# BLDC-MOSFET.net
KiCad netlist of a schematic drawn in Altium Designer
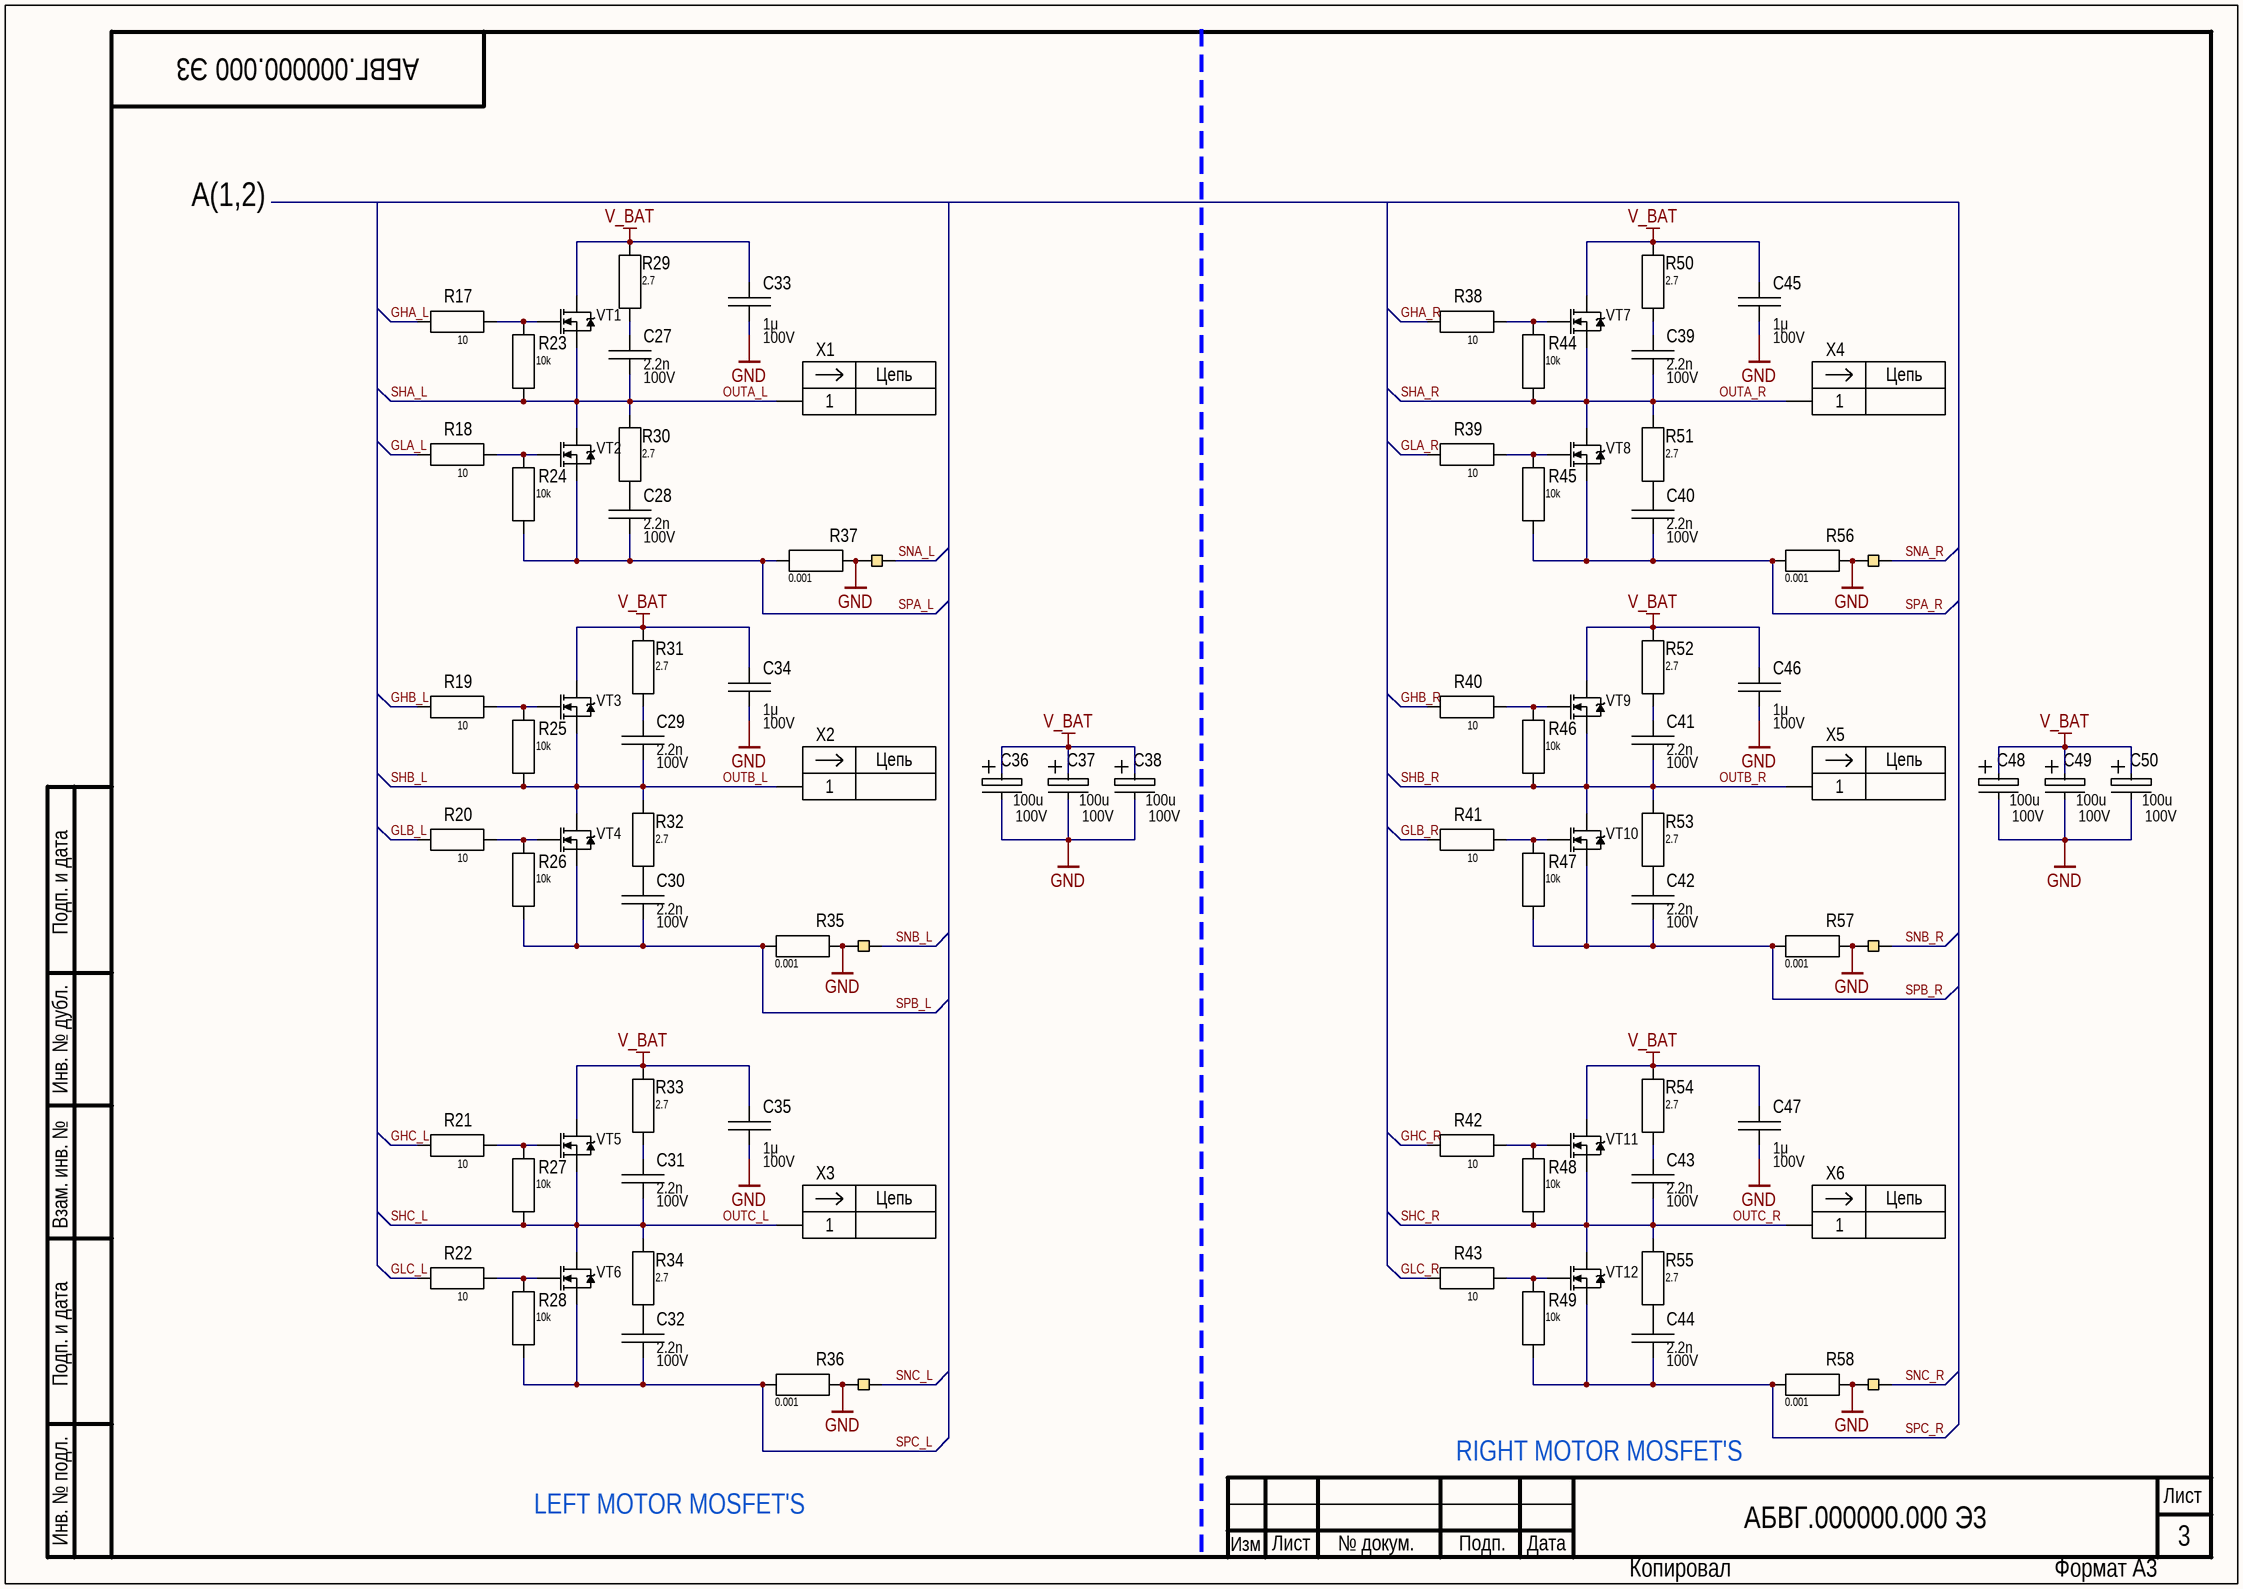
[diagram p0: BLDC-MOSFET.SchDoc]

(export (version "E")
  (design (tool "Eeschema 10.0.6"))
  (components
    (comp (ref "C27")
      (value "2.2n")
      (footprint "StandardCase:CAP: 0603")
      (fields
        (field (name "VALUEMANUFACTURERPARTNUMBER") "Ceramic capacitor, 2.2n, X7R, ±10%, 100V, 0603, -55...+125°C")
        (field (name "TOLERANCE") "±10%")
        (field (name "VOLTAGE") "100V")
      )
      (libsource (lib "Capacitor") (part "Ceramic_0603"))
    )
    (comp (ref "C28")
      (value "2.2n")
      (footprint "StandardCase:CAP: 0603")
      (fields
        (field (name "VALUEMANUFACTURERPARTNUMBER") "Ceramic capacitor, 2.2n, X7R, ±10%, 100V, 0603, -55...+125°C")
        (field (name "TOLERANCE") "±10%")
        (field (name "VOLTAGE") "100V")
      )
      (libsource (lib "Capacitor") (part "Ceramic_0603"))
    )
    (comp (ref "C29")
      (value "2.2n")
      (footprint "StandardCase:CAP: 0603")
      (fields
        (field (name "VALUEMANUFACTURERPARTNUMBER") "Ceramic capacitor, 2.2n, X7R, ±10%, 100V, 0603, -55...+125°C")
        (field (name "TOLERANCE") "±10%")
        (field (name "VOLTAGE") "100V")
      )
      (libsource (lib "Capacitor") (part "Ceramic_0603"))
    )
    (comp (ref "C30")
      (value "2.2n")
      (footprint "StandardCase:CAP: 0603")
      (fields
        (field (name "VALUEMANUFACTURERPARTNUMBER") "Ceramic capacitor, 2.2n, X7R, ±10%, 100V, 0603, -55...+125°C")
        (field (name "TOLERANCE") "±10%")
        (field (name "VOLTAGE") "100V")
      )
      (libsource (lib "Capacitor") (part "Ceramic_0603"))
    )
    (comp (ref "C31")
      (value "2.2n")
      (footprint "StandardCase:CAP: 0603")
      (fields
        (field (name "VALUEMANUFACTURERPARTNUMBER") "Ceramic capacitor, 2.2n, X7R, ±10%, 100V, 0603, -55...+125°C")
        (field (name "TOLERANCE") "±10%")
        (field (name "VOLTAGE") "100V")
      )
      (libsource (lib "Capacitor") (part "Ceramic_0603"))
    )
    (comp (ref "C32")
      (value "2.2n")
      (footprint "StandardCase:CAP: 0603")
      (fields
        (field (name "VALUEMANUFACTURERPARTNUMBER") "Ceramic capacitor, 2.2n, X7R, ±10%, 100V, 0603, -55...+125°C")
        (field (name "TOLERANCE") "±10%")
        (field (name "VOLTAGE") "100V")
      )
      (libsource (lib "Capacitor") (part "Ceramic_0603"))
    )
    (comp (ref "C33")
      (value "1μ")
      (footprint "StandardCase:CAP: 1206")
      (fields
        (field (name "VALUEMANUFACTURERPARTNUMBER") "Ceramic capacitor, 1μ, X7R, ±10%, 100V, 1206, -55...+125°C")
        (field (name "TOLERANCE") "±10%")
        (field (name "VOLTAGE") "100V")
      )
      (libsource (lib "Capacitor") (part "Ceramic_1206"))
    )
    (comp (ref "C34")
      (value "1μ")
      (footprint "StandardCase:CAP: 1206")
      (fields
        (field (name "VALUEMANUFACTURERPARTNUMBER") "Ceramic capacitor, 1μ, X7R, ±10%, 100V, 1206, -55...+125°C")
        (field (name "TOLERANCE") "±10%")
        (field (name "VOLTAGE") "100V")
      )
      (libsource (lib "Capacitor") (part "Ceramic_1206"))
    )
    (comp (ref "C35")
      (value "1μ")
      (footprint "StandardCase:CAP: 1206")
      (fields
        (field (name "VALUEMANUFACTURERPARTNUMBER") "Ceramic capacitor, 1μ, X7R, ±10%, 100V, 1206, -55...+125°C")
        (field (name "TOLERANCE") "±10%")
        (field (name "VOLTAGE") "100V")
      )
      (libsource (lib "Capacitor") (part "Ceramic_1206"))
    )
    (comp (ref "C36")
      (value "100u")
      (footprint "ECR1021")
      (description "ECR1021")
      (fields (field (name "PARTNUMBER") "B45196HM20-35 B-100u мкФ") (field (name "VOLTAGE") "100V"))
      (libsource (lib "capacitors") (part "ECR1021"))
    )
    (comp (ref "C37")
      (value "100u")
      (footprint "ECR1021")
      (description "ECR1021")
      (fields (field (name "PARTNUMBER") "B45196HM20-35 B-100u мкФ") (field (name "VOLTAGE") "100V"))
      (libsource (lib "capacitors") (part "ECR1021"))
    )
    (comp (ref "C38")
      (value "100u")
      (footprint "ECR1021")
      (description "ECR1021")
      (fields (field (name "PARTNUMBER") "B45196HM20-35 B-100u мкФ") (field (name "VOLTAGE") "100V"))
      (libsource (lib "capacitors") (part "ECR1021"))
    )
    (comp (ref "C39")
      (value "2.2n")
      (footprint "StandardCase:CAP: 0603")
      (fields
        (field (name "VALUEMANUFACTURERPARTNUMBER") "Ceramic capacitor, 2.2n, X7R, ±10%, 100V, 0603, -55...+125°C")
        (field (name "TOLERANCE") "±10%")
        (field (name "VOLTAGE") "100V")
      )
      (libsource (lib "Capacitor") (part "Ceramic_0603"))
    )
    (comp (ref "C40")
      (value "2.2n")
      (footprint "StandardCase:CAP: 0603")
      (fields
        (field (name "VALUEMANUFACTURERPARTNUMBER") "Ceramic capacitor, 2.2n, X7R, ±10%, 100V, 0603, -55...+125°C")
        (field (name "TOLERANCE") "±10%")
        (field (name "VOLTAGE") "100V")
      )
      (libsource (lib "Capacitor") (part "Ceramic_0603"))
    )
    (comp (ref "C41")
      (value "2.2n")
      (footprint "StandardCase:CAP: 0603")
      (fields
        (field (name "VALUEMANUFACTURERPARTNUMBER") "Ceramic capacitor, 2.2n, X7R, ±10%, 100V, 0603, -55...+125°C")
        (field (name "TOLERANCE") "±10%")
        (field (name "VOLTAGE") "100V")
      )
      (libsource (lib "Capacitor") (part "Ceramic_0603"))
    )
    (comp (ref "C42")
      (value "2.2n")
      (footprint "StandardCase:CAP: 0603")
      (fields
        (field (name "VALUEMANUFACTURERPARTNUMBER") "Ceramic capacitor, 2.2n, X7R, ±10%, 100V, 0603, -55...+125°C")
        (field (name "TOLERANCE") "±10%")
        (field (name "VOLTAGE") "100V")
      )
      (libsource (lib "Capacitor") (part "Ceramic_0603"))
    )
    (comp (ref "C43")
      (value "2.2n")
      (footprint "StandardCase:CAP: 0603")
      (fields
        (field (name "VALUEMANUFACTURERPARTNUMBER") "Ceramic capacitor, 2.2n, X7R, ±10%, 100V, 0603, -55...+125°C")
        (field (name "TOLERANCE") "±10%")
        (field (name "VOLTAGE") "100V")
      )
      (libsource (lib "Capacitor") (part "Ceramic_0603"))
    )
    (comp (ref "C44")
      (value "2.2n")
      (footprint "StandardCase:CAP: 0603")
      (fields
        (field (name "VALUEMANUFACTURERPARTNUMBER") "Ceramic capacitor, 2.2n, X7R, ±10%, 100V, 0603, -55...+125°C")
        (field (name "TOLERANCE") "±10%")
        (field (name "VOLTAGE") "100V")
      )
      (libsource (lib "Capacitor") (part "Ceramic_0603"))
    )
    (comp (ref "C45")
      (value "1μ")
      (footprint "StandardCase:CAP: 1206")
      (fields
        (field (name "VALUEMANUFACTURERPARTNUMBER") "Ceramic capacitor, 1μ, X7R, ±10%, 100V, 1206, -55...+125°C")
        (field (name "TOLERANCE") "±10%")
        (field (name "VOLTAGE") "100V")
      )
      (libsource (lib "Capacitor") (part "Ceramic_1206"))
    )
    (comp (ref "C46")
      (value "1μ")
      (footprint "StandardCase:CAP: 1206")
      (fields
        (field (name "VALUEMANUFACTURERPARTNUMBER") "Ceramic capacitor, 1μ, X7R, ±10%, 100V, 1206, -55...+125°C")
        (field (name "TOLERANCE") "±10%")
        (field (name "VOLTAGE") "100V")
      )
      (libsource (lib "Capacitor") (part "Ceramic_1206"))
    )
    (comp (ref "C47")
      (value "1μ")
      (footprint "StandardCase:CAP: 1206")
      (fields
        (field (name "VALUEMANUFACTURERPARTNUMBER") "Ceramic capacitor, 1μ, X7R, ±10%, 100V, 1206, -55...+125°C")
        (field (name "TOLERANCE") "±10%")
        (field (name "VOLTAGE") "100V")
      )
      (libsource (lib "Capacitor") (part "Ceramic_1206"))
    )
    (comp (ref "C48")
      (value "100u")
      (footprint "ECR1021")
      (description "ECR1021")
      (fields (field (name "PARTNUMBER") "B45196HM20-35 B-100u мкФ") (field (name "VOLTAGE") "100V"))
      (libsource (lib "capacitors") (part "ECR1021"))
    )
    (comp (ref "C49")
      (value "100u")
      (footprint "ECR1021")
      (description "ECR1021")
      (fields (field (name "PARTNUMBER") "B45196HM20-35 B-100u мкФ") (field (name "VOLTAGE") "100V"))
      (libsource (lib "capacitors") (part "ECR1021"))
    )
    (comp (ref "C50")
      (value "100u")
      (footprint "ECR1021")
      (description "ECR1021")
      (fields (field (name "PARTNUMBER") "B45196HM20-35 B-100u мкФ") (field (name "VOLTAGE") "100V"))
      (libsource (lib "capacitors") (part "ECR1021"))
    )
    (comp (ref "NT1") (value "~") (footprint "CON: NT") (libsource (lib "BKM_SCH_Lib") (part "NT")))
    (comp (ref "NT2") (value "~") (footprint "CON: NT") (libsource (lib "BKM_SCH_Lib") (part "NT")))
    (comp (ref "NT3") (value "~") (footprint "CON: NT") (libsource (lib "BKM_SCH_Lib") (part "NT")))
    (comp (ref "NT4") (value "~") (footprint "CON: NT") (libsource (lib "BKM_SCH_Lib") (part "NT")))
    (comp (ref "NT5") (value "~") (footprint "CON: NT") (libsource (lib "BKM_SCH_Lib") (part "NT")))
    (comp (ref "NT6") (value "~") (footprint "CON: NT") (libsource (lib "BKM_SCH_Lib") (part "NT")))
    (comp (ref "R17")
      (value "10")
      (footprint "RES: 0402")
      (fields (field (name "PARTNUMBER") "RC0402FR-071KL") (field (name "TOLERANCE") "1%"))
      (libsource (lib "Fider_Board_Lib") (part "RES 0402"))
    )
    (comp (ref "R18")
      (value "10")
      (footprint "RES: 0402")
      (fields (field (name "PARTNUMBER") "RC0402FR-071KL") (field (name "TOLERANCE") "1%"))
      (libsource (lib "Fider_Board_Lib") (part "RES 0402"))
    )
    (comp (ref "R19")
      (value "10")
      (footprint "RES: 0402")
      (fields (field (name "PARTNUMBER") "RC0402FR-071KL") (field (name "TOLERANCE") "1%"))
      (libsource (lib "Fider_Board_Lib") (part "RES 0402"))
    )
    (comp (ref "R20")
      (value "10")
      (footprint "RES: 0402")
      (fields (field (name "PARTNUMBER") "RC0402FR-071KL") (field (name "TOLERANCE") "1%"))
      (libsource (lib "Fider_Board_Lib") (part "RES 0402"))
    )
    (comp (ref "R21")
      (value "10")
      (footprint "RES: 0402")
      (fields (field (name "PARTNUMBER") "RC0402FR-071KL") (field (name "TOLERANCE") "1%"))
      (libsource (lib "Fider_Board_Lib") (part "RES 0402"))
    )
    (comp (ref "R22")
      (value "10")
      (footprint "RES: 0402")
      (fields (field (name "PARTNUMBER") "RC0402FR-071KL") (field (name "TOLERANCE") "1%"))
      (libsource (lib "Fider_Board_Lib") (part "RES 0402"))
    )
    (comp (ref "R23")
      (value "10k")
      (footprint "RES: 0402")
      (fields (field (name "TOLERANCE") "1%"))
      (libsource (lib "BKM_SCH_Lib") (part "RES 0402"))
    )
    (comp (ref "R24")
      (value "10k")
      (footprint "RES: 0402")
      (fields (field (name "TOLERANCE") "1%"))
      (libsource (lib "BKM_SCH_Lib") (part "RES 0402"))
    )
    (comp (ref "R25")
      (value "10k")
      (footprint "RES: 0402")
      (fields (field (name "TOLERANCE") "1%"))
      (libsource (lib "BKM_SCH_Lib") (part "RES 0402"))
    )
    (comp (ref "R26")
      (value "10k")
      (footprint "RES: 0402")
      (fields (field (name "TOLERANCE") "1%"))
      (libsource (lib "BKM_SCH_Lib") (part "RES 0402"))
    )
    (comp (ref "R27")
      (value "10k")
      (footprint "RES: 0402")
      (fields (field (name "TOLERANCE") "1%"))
      (libsource (lib "BKM_SCH_Lib") (part "RES 0402"))
    )
    (comp (ref "R28")
      (value "10k")
      (footprint "RES: 0402")
      (fields (field (name "TOLERANCE") "1%"))
      (libsource (lib "BKM_SCH_Lib") (part "RES 0402"))
    )
    (comp (ref "R29") (value "2.7") (footprint "RES: 0805") (libsource (lib "BKM_SCH_Lib") (part "RES 0805")))
    (comp (ref "R30") (value "2.7") (footprint "RES: 0805") (libsource (lib "BKM_SCH_Lib") (part "RES 0805")))
    (comp (ref "R31") (value "2.7") (footprint "RES: 0805") (libsource (lib "BKM_SCH_Lib") (part "RES 0805")))
    (comp (ref "R32") (value "2.7") (footprint "RES: 0805") (libsource (lib "BKM_SCH_Lib") (part "RES 0805")))
    (comp (ref "R33") (value "2.7") (footprint "RES: 0805") (libsource (lib "BKM_SCH_Lib") (part "RES 0805")))
    (comp (ref "R34") (value "2.7") (footprint "RES: 0805") (libsource (lib "BKM_SCH_Lib") (part "RES 0805")))
    (comp (ref "R35")
      (value "0.001")
      (footprint "RES: 2512")
      (fields (field (name "PARTNUMBER") "CST0612-FC-R001E"))
      (libsource (lib "Fider_Board_Lib") (part "RES 2512"))
    )
    (comp (ref "R36")
      (value "0.001")
      (footprint "RES: 2512")
      (fields (field (name "PARTNUMBER") "CST0612-FC-R001E"))
      (libsource (lib "Fider_Board_Lib") (part "RES 2512"))
    )
    (comp (ref "R37")
      (value "0.001")
      (footprint "RES: 2512")
      (fields (field (name "PARTNUMBER") "CST0612-FC-R001E"))
      (libsource (lib "Fider_Board_Lib") (part "RES 2512"))
    )
    (comp (ref "R38")
      (value "10")
      (footprint "RES: 0402")
      (fields (field (name "PARTNUMBER") "RC0402FR-071KL") (field (name "TOLERANCE") "1%"))
      (libsource (lib "Fider_Board_Lib") (part "RES 0402"))
    )
    (comp (ref "R39")
      (value "10")
      (footprint "RES: 0402")
      (fields (field (name "PARTNUMBER") "RC0402FR-071KL") (field (name "TOLERANCE") "1%"))
      (libsource (lib "Fider_Board_Lib") (part "RES 0402"))
    )
    (comp (ref "R40")
      (value "10")
      (footprint "RES: 0402")
      (fields (field (name "PARTNUMBER") "RC0402FR-071KL") (field (name "TOLERANCE") "1%"))
      (libsource (lib "Fider_Board_Lib") (part "RES 0402"))
    )
    (comp (ref "R41")
      (value "10")
      (footprint "RES: 0402")
      (fields (field (name "PARTNUMBER") "RC0402FR-071KL") (field (name "TOLERANCE") "1%"))
      (libsource (lib "Fider_Board_Lib") (part "RES 0402"))
    )
    (comp (ref "R42")
      (value "10")
      (footprint "RES: 0402")
      (fields (field (name "PARTNUMBER") "RC0402FR-071KL") (field (name "TOLERANCE") "1%"))
      (libsource (lib "Fider_Board_Lib") (part "RES 0402"))
    )
    (comp (ref "R43")
      (value "10")
      (footprint "RES: 0402")
      (fields (field (name "PARTNUMBER") "RC0402FR-071KL") (field (name "TOLERANCE") "1%"))
      (libsource (lib "Fider_Board_Lib") (part "RES 0402"))
    )
    (comp (ref "R44")
      (value "10k")
      (footprint "RES: 0402")
      (fields (field (name "TOLERANCE") "1%"))
      (libsource (lib "BKM_SCH_Lib") (part "RES 0402"))
    )
    (comp (ref "R45")
      (value "10k")
      (footprint "RES: 0402")
      (fields (field (name "TOLERANCE") "1%"))
      (libsource (lib "BKM_SCH_Lib") (part "RES 0402"))
    )
    (comp (ref "R46")
      (value "10k")
      (footprint "RES: 0402")
      (fields (field (name "TOLERANCE") "1%"))
      (libsource (lib "BKM_SCH_Lib") (part "RES 0402"))
    )
    (comp (ref "R47")
      (value "10k")
      (footprint "RES: 0402")
      (fields (field (name "TOLERANCE") "1%"))
      (libsource (lib "BKM_SCH_Lib") (part "RES 0402"))
    )
    (comp (ref "R48")
      (value "10k")
      (footprint "RES: 0402")
      (fields (field (name "TOLERANCE") "1%"))
      (libsource (lib "BKM_SCH_Lib") (part "RES 0402"))
    )
    (comp (ref "R49")
      (value "10k")
      (footprint "RES: 0402")
      (fields (field (name "TOLERANCE") "1%"))
      (libsource (lib "BKM_SCH_Lib") (part "RES 0402"))
    )
    (comp (ref "R50") (value "2.7") (footprint "RES: 0805") (libsource (lib "BKM_SCH_Lib") (part "RES 0805")))
    (comp (ref "R51") (value "2.7") (footprint "RES: 0805") (libsource (lib "BKM_SCH_Lib") (part "RES 0805")))
    (comp (ref "R52") (value "2.7") (footprint "RES: 0805") (libsource (lib "BKM_SCH_Lib") (part "RES 0805")))
    (comp (ref "R53") (value "2.7") (footprint "RES: 0805") (libsource (lib "BKM_SCH_Lib") (part "RES 0805")))
    (comp (ref "R54") (value "2.7") (footprint "RES: 0805") (libsource (lib "BKM_SCH_Lib") (part "RES 0805")))
    (comp (ref "R55") (value "2.7") (footprint "RES: 0805") (libsource (lib "BKM_SCH_Lib") (part "RES 0805")))
    (comp (ref "R56")
      (value "0.001")
      (footprint "RES: 2512")
      (fields (field (name "PARTNUMBER") "CST0612-FC-R001E"))
      (libsource (lib "Fider_Board_Lib") (part "RES 2512"))
    )
    (comp (ref "R57")
      (value "0.001")
      (footprint "RES: 2512")
      (fields (field (name "PARTNUMBER") "CST0612-FC-R001E"))
      (libsource (lib "Fider_Board_Lib") (part "RES 2512"))
    )
    (comp (ref "R58")
      (value "0.001")
      (footprint "RES: 2512")
      (fields (field (name "PARTNUMBER") "CST0612-FC-R001E"))
      (libsource (lib "Fider_Board_Lib") (part "RES 2512"))
    )
    (comp (ref "VT1")
      (value "~")
      (footprint "DirectFET MZ")
      (fields
        (field (name "MANUFACTURER") "Infineon Technologies")
        (field (name "VALUEMANUFACTURERPARTNUMBER") "MOSFET N-channel transistor, 150V, 35A, 9.1nC, 2.5W, 29mOhm, 756pF, DIRECTFET-MZ, -55...+150°C")
        (field (name "PARTNUMBER") "IRF6643TRPBF")
      )
      (libsource (lib "Transistor") (part "MOSFET_N_123"))
    )
    (comp (ref "VT2")
      (value "~")
      (footprint "DirectFET MZ")
      (fields
        (field (name "MANUFACTURER") "Infineon Technologies")
        (field (name "VALUEMANUFACTURERPARTNUMBER") "MOSFET N-channel transistor, 150V, 35A, 9.1nC, 2.5W, 29mOhm, 756pF, DIRECTFET-MZ, -55...+150°C")
        (field (name "PARTNUMBER") "IRF6643TRPBF")
      )
      (libsource (lib "Transistor") (part "MOSFET_N_123"))
    )
    (comp (ref "VT3")
      (value "~")
      (footprint "DirectFET MZ")
      (fields
        (field (name "MANUFACTURER") "Infineon Technologies")
        (field (name "VALUEMANUFACTURERPARTNUMBER") "MOSFET N-channel transistor, 150V, 35A, 9.1nC, 2.5W, 29mOhm, 756pF, DIRECTFET-MZ, -55...+150°C")
        (field (name "PARTNUMBER") "IRF6643TRPBF")
      )
      (libsource (lib "Transistor") (part "MOSFET_N_123"))
    )
    (comp (ref "VT4")
      (value "~")
      (footprint "DirectFET MZ")
      (fields
        (field (name "MANUFACTURER") "Infineon Technologies")
        (field (name "VALUEMANUFACTURERPARTNUMBER") "MOSFET N-channel transistor, 150V, 35A, 9.1nC, 2.5W, 29mOhm, 756pF, DIRECTFET-MZ, -55...+150°C")
        (field (name "PARTNUMBER") "IRF6643TRPBF")
      )
      (libsource (lib "Transistor") (part "MOSFET_N_123"))
    )
    (comp (ref "VT5")
      (value "~")
      (footprint "DirectFET MZ")
      (fields
        (field (name "MANUFACTURER") "Infineon Technologies")
        (field (name "VALUEMANUFACTURERPARTNUMBER") "MOSFET N-channel transistor, 150V, 35A, 9.1nC, 2.5W, 29mOhm, 756pF, DIRECTFET-MZ, -55...+150°C")
        (field (name "PARTNUMBER") "IRF6643TRPBF")
      )
      (libsource (lib "Transistor") (part "MOSFET_N_123"))
    )
    (comp (ref "VT6")
      (value "~")
      (footprint "DirectFET MZ")
      (fields
        (field (name "MANUFACTURER") "Infineon Technologies")
        (field (name "VALUEMANUFACTURERPARTNUMBER") "MOSFET N-channel transistor, 150V, 35A, 9.1nC, 2.5W, 29mOhm, 756pF, DIRECTFET-MZ, -55...+150°C")
        (field (name "PARTNUMBER") "IRF6643TRPBF")
      )
      (libsource (lib "Transistor") (part "MOSFET_N_123"))
    )
    (comp (ref "VT7")
      (value "~")
      (footprint "DirectFET MZ")
      (fields
        (field (name "MANUFACTURER") "Infineon Technologies")
        (field (name "VALUEMANUFACTURERPARTNUMBER") "MOSFET N-channel transistor, 150V, 35A, 9.1nC, 2.5W, 29mOhm, 756pF, DIRECTFET-MZ, -55...+150°C")
        (field (name "PARTNUMBER") "IRF6643TRPBF")
      )
      (libsource (lib "Transistor") (part "MOSFET_N_123"))
    )
    (comp (ref "VT8")
      (value "~")
      (footprint "DirectFET MZ")
      (fields
        (field (name "MANUFACTURER") "Infineon Technologies")
        (field (name "VALUEMANUFACTURERPARTNUMBER") "MOSFET N-channel transistor, 150V, 35A, 9.1nC, 2.5W, 29mOhm, 756pF, DIRECTFET-MZ, -55...+150°C")
        (field (name "PARTNUMBER") "IRF6643TRPBF")
      )
      (libsource (lib "Transistor") (part "MOSFET_N_123"))
    )
    (comp (ref "VT9")
      (value "~")
      (footprint "DirectFET MZ")
      (fields
        (field (name "MANUFACTURER") "Infineon Technologies")
        (field (name "VALUEMANUFACTURERPARTNUMBER") "MOSFET N-channel transistor, 150V, 35A, 9.1nC, 2.5W, 29mOhm, 756pF, DIRECTFET-MZ, -55...+150°C")
        (field (name "PARTNUMBER") "IRF6643TRPBF")
      )
      (libsource (lib "Transistor") (part "MOSFET_N_123"))
    )
    (comp (ref "VT10")
      (value "~")
      (footprint "DirectFET MZ")
      (fields
        (field (name "MANUFACTURER") "Infineon Technologies")
        (field (name "VALUEMANUFACTURERPARTNUMBER") "MOSFET N-channel transistor, 150V, 35A, 9.1nC, 2.5W, 29mOhm, 756pF, DIRECTFET-MZ, -55...+150°C")
        (field (name "PARTNUMBER") "IRF6643TRPBF")
      )
      (libsource (lib "Transistor") (part "MOSFET_N_123"))
    )
    (comp (ref "VT11")
      (value "~")
      (footprint "DirectFET MZ")
      (fields
        (field (name "MANUFACTURER") "Infineon Technologies")
        (field (name "VALUEMANUFACTURERPARTNUMBER") "MOSFET N-channel transistor, 150V, 35A, 9.1nC, 2.5W, 29mOhm, 756pF, DIRECTFET-MZ, -55...+150°C")
        (field (name "PARTNUMBER") "IRF6643TRPBF")
      )
      (libsource (lib "Transistor") (part "MOSFET_N_123"))
    )
    (comp (ref "VT12")
      (value "~")
      (footprint "DirectFET MZ")
      (fields
        (field (name "MANUFACTURER") "Infineon Technologies")
        (field (name "VALUEMANUFACTURERPARTNUMBER") "MOSFET N-channel transistor, 150V, 35A, 9.1nC, 2.5W, 29mOhm, 756pF, DIRECTFET-MZ, -55...+150°C")
        (field (name "PARTNUMBER") "IRF6643TRPBF")
      )
      (libsource (lib "Transistor") (part "MOSFET_N_123"))
    )
    (comp (ref "X1")
      (value "DJ617-6.3 (TA-MR1)")
      (footprint "CON: DJ617-6.3 (TA-MR1)")
      (libsource (lib "BKM_SCH_Lib") (part "DJ617-6.3 (TA-MR1)"))
    )
    (comp (ref "X2")
      (value "DJ617-6.3 (TA-MR1)")
      (footprint "CON: DJ617-6.3 (TA-MR1)")
      (libsource (lib "BKM_SCH_Lib") (part "DJ617-6.3 (TA-MR1)"))
    )
    (comp (ref "X3")
      (value "DJ617-6.3 (TA-MR1)")
      (footprint "CON: DJ617-6.3 (TA-MR1)")
      (libsource (lib "BKM_SCH_Lib") (part "DJ617-6.3 (TA-MR1)"))
    )
    (comp (ref "X4")
      (value "DJ617-6.3 (TA-MR1)")
      (footprint "CON: DJ617-6.3 (TA-MR1)")
      (libsource (lib "BKM_SCH_Lib") (part "DJ617-6.3 (TA-MR1)"))
    )
    (comp (ref "X5")
      (value "DJ617-6.3 (TA-MR1)")
      (footprint "CON: DJ617-6.3 (TA-MR1)")
      (libsource (lib "BKM_SCH_Lib") (part "DJ617-6.3 (TA-MR1)"))
    )
    (comp (ref "X6")
      (value "DJ617-6.3 (TA-MR1)")
      (footprint "CON: DJ617-6.3 (TA-MR1)")
      (libsource (lib "BKM_SCH_Lib") (part "DJ617-6.3 (TA-MR1)"))
    )
  )
  (nets
    (net (code "2") (name "/GHA_L") (class "Default")
      (node (ref "R17") (pin "2") (pinfunction "2_2") (pintype "passive"))
    )
    (net (code "3") (name "/GHA_R") (class "Default")
      (node (ref "R38") (pin "2") (pinfunction "2_2") (pintype "passive"))
    )
    (net (code "4") (name "/GHB_L") (class "Default")
      (node (ref "R19") (pin "2") (pinfunction "2_2") (pintype "passive"))
    )
    (net (code "5") (name "/GHB_R") (class "Default")
      (node (ref "R40") (pin "2") (pinfunction "2_2") (pintype "passive"))
    )
    (net (code "6") (name "/GHC_L") (class "Default")
      (node (ref "R21") (pin "2") (pinfunction "2_2") (pintype "passive"))
    )
    (net (code "7") (name "/GHC_R") (class "Default")
      (node (ref "R42") (pin "2") (pinfunction "2_2") (pintype "passive"))
    )
    (net (code "8") (name "/GLA_L") (class "Default")
      (node (ref "R18") (pin "2") (pinfunction "2_2") (pintype "passive"))
    )
    (net (code "9") (name "/GLA_R") (class "Default")
      (node (ref "R39") (pin "2") (pinfunction "2_2") (pintype "passive"))
    )
    (net (code "10") (name "/GLB_L") (class "Default")
      (node (ref "R20") (pin "2") (pinfunction "2_2") (pintype "passive"))
    )
    (net (code "11") (name "/GLB_R") (class "Default")
      (node (ref "R41") (pin "2") (pinfunction "2_2") (pintype "passive"))
    )
    (net (code "12") (name "/GLC_L") (class "Default")
      (node (ref "R22") (pin "2") (pinfunction "2_2") (pintype "passive"))
    )
    (net (code "13") (name "/GLC_R") (class "Default")
      (node (ref "R43") (pin "2") (pinfunction "2_2") (pintype "passive"))
    )
    (net (code "14") (name "/OUTA_L") (class "Default")
      (node (ref "C27") (pin "1") (pinfunction "1_1") (pintype "power_in"))
      (node (ref "R23") (pin "1") (pinfunction "1_1") (pintype "passive"))
      (node (ref "R30") (pin "2") (pinfunction "2_2") (pintype "passive"))
      (node (ref "VT1") (pin "3") (pinfunction "S_3") (pintype "passive"))
      (node (ref "VT2") (pin "2") (pinfunction "D_2") (pintype "passive"))
      (node (ref "X1") (pin "1") (pinfunction "1_1") (pintype "passive"))
    )
    (net (code "15") (name "/OUTA_R") (class "Default")
      (node (ref "C39") (pin "1") (pinfunction "1_1") (pintype "power_in"))
      (node (ref "R44") (pin "1") (pinfunction "1_1") (pintype "passive"))
      (node (ref "R51") (pin "2") (pinfunction "2_2") (pintype "passive"))
      (node (ref "VT7") (pin "3") (pinfunction "S_3") (pintype "passive"))
      (node (ref "VT8") (pin "2") (pinfunction "D_2") (pintype "passive"))
      (node (ref "X4") (pin "1") (pinfunction "1_1") (pintype "passive"))
    )
    (net (code "16") (name "/OUTB_L") (class "Default")
      (node (ref "C29") (pin "1") (pinfunction "1_1") (pintype "power_in"))
      (node (ref "R25") (pin "1") (pinfunction "1_1") (pintype "passive"))
      (node (ref "R32") (pin "2") (pinfunction "2_2") (pintype "passive"))
      (node (ref "VT3") (pin "3") (pinfunction "S_3") (pintype "passive"))
      (node (ref "VT4") (pin "2") (pinfunction "D_2") (pintype "passive"))
      (node (ref "X2") (pin "1") (pinfunction "1_1") (pintype "passive"))
    )
    (net (code "17") (name "/OUTB_R") (class "Default")
      (node (ref "C41") (pin "1") (pinfunction "1_1") (pintype "power_in"))
      (node (ref "R46") (pin "1") (pinfunction "1_1") (pintype "passive"))
      (node (ref "R53") (pin "2") (pinfunction "2_2") (pintype "passive"))
      (node (ref "VT10") (pin "2") (pinfunction "D_2") (pintype "passive"))
      (node (ref "VT9") (pin "3") (pinfunction "S_3") (pintype "passive"))
      (node (ref "X5") (pin "1") (pinfunction "1_1") (pintype "passive"))
    )
    (net (code "18") (name "/OUTC_L") (class "Default")
      (node (ref "C31") (pin "1") (pinfunction "1_1") (pintype "power_in"))
      (node (ref "R27") (pin "1") (pinfunction "1_1") (pintype "passive"))
      (node (ref "R34") (pin "2") (pinfunction "2_2") (pintype "passive"))
      (node (ref "VT5") (pin "3") (pinfunction "S_3") (pintype "passive"))
      (node (ref "VT6") (pin "2") (pinfunction "D_2") (pintype "passive"))
      (node (ref "X3") (pin "1") (pinfunction "1_1") (pintype "passive"))
    )
    (net (code "19") (name "/OUTC_R") (class "Default")
      (node (ref "C43") (pin "1") (pinfunction "1_1") (pintype "power_in"))
      (node (ref "R48") (pin "1") (pinfunction "1_1") (pintype "passive"))
      (node (ref "R55") (pin "2") (pinfunction "2_2") (pintype "passive"))
      (node (ref "VT11") (pin "3") (pinfunction "S_3") (pintype "passive"))
      (node (ref "VT12") (pin "2") (pinfunction "D_2") (pintype "passive"))
      (node (ref "X6") (pin "1") (pinfunction "1_1") (pintype "passive"))
    )
    (net (code "20") (name "/SNA_L") (class "Default")
      (node (ref "NT3") (pin "2") (pinfunction "2_2") (pintype "passive"))
    )
    (net (code "21") (name "/SNA_R") (class "Default")
      (node (ref "NT4") (pin "2") (pinfunction "2_2") (pintype "passive"))
    )
    (net (code "22") (name "/SNB_L") (class "Default")
      (node (ref "NT1") (pin "2") (pinfunction "2_2") (pintype "passive"))
    )
    (net (code "23") (name "/SNB_R") (class "Default")
      (node (ref "NT5") (pin "2") (pinfunction "2_2") (pintype "passive"))
    )
    (net (code "24") (name "/SNC_L") (class "Default")
      (node (ref "NT2") (pin "2") (pinfunction "2_2") (pintype "passive"))
    )
    (net (code "25") (name "/SNC_R") (class "Default")
      (node (ref "NT6") (pin "2") (pinfunction "2_2") (pintype "passive"))
    )
    (net (code "26") (name "/SPA_L") (class "Default")
      (node (ref "C28") (pin "1") (pinfunction "1_1") (pintype "power_in"))
      (node (ref "R24") (pin "1") (pinfunction "1_1") (pintype "passive"))
      (node (ref "R37") (pin "2") (pinfunction "2_2") (pintype "passive"))
      (node (ref "VT2") (pin "3") (pinfunction "S_3") (pintype "passive"))
    )
    (net (code "27") (name "/SPA_R") (class "Default")
      (node (ref "C40") (pin "1") (pinfunction "1_1") (pintype "power_in"))
      (node (ref "R45") (pin "1") (pinfunction "1_1") (pintype "passive"))
      (node (ref "R56") (pin "2") (pinfunction "2_2") (pintype "passive"))
      (node (ref "VT8") (pin "3") (pinfunction "S_3") (pintype "passive"))
    )
    (net (code "28") (name "/SPB_L") (class "Default")
      (node (ref "C30") (pin "1") (pinfunction "1_1") (pintype "power_in"))
      (node (ref "R26") (pin "1") (pinfunction "1_1") (pintype "passive"))
      (node (ref "R35") (pin "2") (pinfunction "2_2") (pintype "passive"))
      (node (ref "VT4") (pin "3") (pinfunction "S_3") (pintype "passive"))
    )
    (net (code "29") (name "/SPB_R") (class "Default")
      (node (ref "C42") (pin "1") (pinfunction "1_1") (pintype "power_in"))
      (node (ref "R47") (pin "1") (pinfunction "1_1") (pintype "passive"))
      (node (ref "R57") (pin "2") (pinfunction "2_2") (pintype "passive"))
      (node (ref "VT10") (pin "3") (pinfunction "S_3") (pintype "passive"))
    )
    (net (code "30") (name "/SPC_L") (class "Default")
      (node (ref "C32") (pin "1") (pinfunction "1_1") (pintype "power_in"))
      (node (ref "R28") (pin "1") (pinfunction "1_1") (pintype "passive"))
      (node (ref "R36") (pin "2") (pinfunction "2_2") (pintype "passive"))
      (node (ref "VT6") (pin "3") (pinfunction "S_3") (pintype "passive"))
    )
    (net (code "31") (name "/SPC_R") (class "Default")
      (node (ref "C44") (pin "1") (pinfunction "1_1") (pintype "power_in"))
      (node (ref "R49") (pin "1") (pinfunction "1_1") (pintype "passive"))
      (node (ref "R58") (pin "2") (pinfunction "2_2") (pintype "passive"))
      (node (ref "VT12") (pin "3") (pinfunction "S_3") (pintype "passive"))
    )
    (net (code "32") (name "GND") (class "Default")
      (node (ref "C33") (pin "1") (pinfunction "1_1") (pintype "power_in"))
      (node (ref "C34") (pin "1") (pinfunction "1_1") (pintype "power_in"))
      (node (ref "C35") (pin "1") (pinfunction "1_1") (pintype "power_in"))
      (node (ref "C36") (pin "2") (pinfunction "2_2") (pintype "passive"))
      (node (ref "C37") (pin "2") (pinfunction "2_2") (pintype "passive"))
      (node (ref "C38") (pin "2") (pinfunction "2_2") (pintype "passive"))
      (node (ref "C45") (pin "1") (pinfunction "1_1") (pintype "power_in"))
      (node (ref "C46") (pin "1") (pinfunction "1_1") (pintype "power_in"))
      (node (ref "C47") (pin "1") (pinfunction "1_1") (pintype "power_in"))
      (node (ref "C48") (pin "2") (pinfunction "2_2") (pintype "passive"))
      (node (ref "C49") (pin "2") (pinfunction "2_2") (pintype "passive"))
      (node (ref "C50") (pin "2") (pinfunction "2_2") (pintype "passive"))
      (node (ref "NT1") (pin "1") (pinfunction "1_1") (pintype "passive"))
      (node (ref "NT2") (pin "1") (pinfunction "1_1") (pintype "passive"))
      (node (ref "NT3") (pin "1") (pinfunction "1_1") (pintype "passive"))
      (node (ref "NT4") (pin "1") (pinfunction "1_1") (pintype "passive"))
      (node (ref "NT5") (pin "1") (pinfunction "1_1") (pintype "passive"))
      (node (ref "NT6") (pin "1") (pinfunction "1_1") (pintype "passive"))
      (node (ref "R35") (pin "1") (pinfunction "1_1") (pintype "passive"))
      (node (ref "R36") (pin "1") (pinfunction "1_1") (pintype "passive"))
      (node (ref "R37") (pin "1") (pinfunction "1_1") (pintype "passive"))
      (node (ref "R56") (pin "1") (pinfunction "1_1") (pintype "passive"))
      (node (ref "R57") (pin "1") (pinfunction "1_1") (pintype "passive"))
      (node (ref "R58") (pin "1") (pinfunction "1_1") (pintype "passive"))
    )
    (net (code "33") (name "Net-(C27-Pad2)") (class "Default")
      (node (ref "C27") (pin "2") (pinfunction "2_2") (pintype "power_in"))
      (node (ref "R29") (pin "1") (pinfunction "1_1") (pintype "passive"))
    )
    (net (code "34") (name "Net-(C28-Pad2)") (class "Default")
      (node (ref "C28") (pin "2") (pinfunction "2_2") (pintype "power_in"))
      (node (ref "R30") (pin "1") (pinfunction "1_1") (pintype "passive"))
    )
    (net (code "35") (name "Net-(C29-Pad2)") (class "Default")
      (node (ref "C29") (pin "2") (pinfunction "2_2") (pintype "power_in"))
      (node (ref "R31") (pin "1") (pinfunction "1_1") (pintype "passive"))
    )
    (net (code "36") (name "Net-(C30-Pad2)") (class "Default")
      (node (ref "C30") (pin "2") (pinfunction "2_2") (pintype "power_in"))
      (node (ref "R32") (pin "1") (pinfunction "1_1") (pintype "passive"))
    )
    (net (code "37") (name "Net-(C31-Pad2)") (class "Default")
      (node (ref "C31") (pin "2") (pinfunction "2_2") (pintype "power_in"))
      (node (ref "R33") (pin "1") (pinfunction "1_1") (pintype "passive"))
    )
    (net (code "38") (name "Net-(C32-Pad2)") (class "Default")
      (node (ref "C32") (pin "2") (pinfunction "2_2") (pintype "power_in"))
      (node (ref "R34") (pin "1") (pinfunction "1_1") (pintype "passive"))
    )
    (net (code "39") (name "Net-(C39-Pad2)") (class "Default")
      (node (ref "C39") (pin "2") (pinfunction "2_2") (pintype "power_in"))
      (node (ref "R50") (pin "1") (pinfunction "1_1") (pintype "passive"))
    )
    (net (code "40") (name "Net-(C40-Pad2)") (class "Default")
      (node (ref "C40") (pin "2") (pinfunction "2_2") (pintype "power_in"))
      (node (ref "R51") (pin "1") (pinfunction "1_1") (pintype "passive"))
    )
    (net (code "41") (name "Net-(C41-Pad2)") (class "Default")
      (node (ref "C41") (pin "2") (pinfunction "2_2") (pintype "power_in"))
      (node (ref "R52") (pin "1") (pinfunction "1_1") (pintype "passive"))
    )
    (net (code "42") (name "Net-(C42-Pad2)") (class "Default")
      (node (ref "C42") (pin "2") (pinfunction "2_2") (pintype "power_in"))
      (node (ref "R53") (pin "1") (pinfunction "1_1") (pintype "passive"))
    )
    (net (code "43") (name "Net-(C43-Pad2)") (class "Default")
      (node (ref "C43") (pin "2") (pinfunction "2_2") (pintype "power_in"))
      (node (ref "R54") (pin "1") (pinfunction "1_1") (pintype "passive"))
    )
    (net (code "44") (name "Net-(C44-Pad2)") (class "Default")
      (node (ref "C44") (pin "2") (pinfunction "2_2") (pintype "power_in"))
      (node (ref "R55") (pin "1") (pinfunction "1_1") (pintype "passive"))
    )
    (net (code "45") (name "Net-(VT1-G)") (class "Default")
      (node (ref "R17") (pin "1") (pinfunction "1_1") (pintype "passive"))
      (node (ref "R23") (pin "2") (pinfunction "2_2") (pintype "passive"))
      (node (ref "VT1") (pin "1") (pinfunction "G_1") (pintype "passive"))
    )
    (net (code "46") (name "Net-(VT2-G)") (class "Default")
      (node (ref "R18") (pin "1") (pinfunction "1_1") (pintype "passive"))
      (node (ref "R24") (pin "2") (pinfunction "2_2") (pintype "passive"))
      (node (ref "VT2") (pin "1") (pinfunction "G_1") (pintype "passive"))
    )
    (net (code "47") (name "Net-(VT3-G)") (class "Default")
      (node (ref "R19") (pin "1") (pinfunction "1_1") (pintype "passive"))
      (node (ref "R25") (pin "2") (pinfunction "2_2") (pintype "passive"))
      (node (ref "VT3") (pin "1") (pinfunction "G_1") (pintype "passive"))
    )
    (net (code "48") (name "Net-(VT4-G)") (class "Default")
      (node (ref "R20") (pin "1") (pinfunction "1_1") (pintype "passive"))
      (node (ref "R26") (pin "2") (pinfunction "2_2") (pintype "passive"))
      (node (ref "VT4") (pin "1") (pinfunction "G_1") (pintype "passive"))
    )
    (net (code "49") (name "Net-(VT5-G)") (class "Default")
      (node (ref "R21") (pin "1") (pinfunction "1_1") (pintype "passive"))
      (node (ref "R27") (pin "2") (pinfunction "2_2") (pintype "passive"))
      (node (ref "VT5") (pin "1") (pinfunction "G_1") (pintype "passive"))
    )
    (net (code "50") (name "Net-(VT6-G)") (class "Default")
      (node (ref "R22") (pin "1") (pinfunction "1_1") (pintype "passive"))
      (node (ref "R28") (pin "2") (pinfunction "2_2") (pintype "passive"))
      (node (ref "VT6") (pin "1") (pinfunction "G_1") (pintype "passive"))
    )
    (net (code "51") (name "Net-(VT7-G)") (class "Default")
      (node (ref "R38") (pin "1") (pinfunction "1_1") (pintype "passive"))
      (node (ref "R44") (pin "2") (pinfunction "2_2") (pintype "passive"))
      (node (ref "VT7") (pin "1") (pinfunction "G_1") (pintype "passive"))
    )
    (net (code "52") (name "Net-(VT8-G)") (class "Default")
      (node (ref "R39") (pin "1") (pinfunction "1_1") (pintype "passive"))
      (node (ref "R45") (pin "2") (pinfunction "2_2") (pintype "passive"))
      (node (ref "VT8") (pin "1") (pinfunction "G_1") (pintype "passive"))
    )
    (net (code "53") (name "Net-(VT9-G)") (class "Default")
      (node (ref "R40") (pin "1") (pinfunction "1_1") (pintype "passive"))
      (node (ref "R46") (pin "2") (pinfunction "2_2") (pintype "passive"))
      (node (ref "VT9") (pin "1") (pinfunction "G_1") (pintype "passive"))
    )
    (net (code "54") (name "Net-(VT10-G)") (class "Default")
      (node (ref "R41") (pin "1") (pinfunction "1_1") (pintype "passive"))
      (node (ref "R47") (pin "2") (pinfunction "2_2") (pintype "passive"))
      (node (ref "VT10") (pin "1") (pinfunction "G_1") (pintype "passive"))
    )
    (net (code "55") (name "Net-(VT11-G)") (class "Default")
      (node (ref "R42") (pin "1") (pinfunction "1_1") (pintype "passive"))
      (node (ref "R48") (pin "2") (pinfunction "2_2") (pintype "passive"))
      (node (ref "VT11") (pin "1") (pinfunction "G_1") (pintype "passive"))
    )
    (net (code "56") (name "Net-(VT12-G)") (class "Default")
      (node (ref "R43") (pin "1") (pinfunction "1_1") (pintype "passive"))
      (node (ref "R49") (pin "2") (pinfunction "2_2") (pintype "passive"))
      (node (ref "VT12") (pin "1") (pinfunction "G_1") (pintype "passive"))
    )
    (net (code "57") (name "V_BAT") (class "Default")
      (node (ref "C33") (pin "2") (pinfunction "2_2") (pintype "power_in"))
      (node (ref "C34") (pin "2") (pinfunction "2_2") (pintype "power_in"))
      (node (ref "C35") (pin "2") (pinfunction "2_2") (pintype "power_in"))
      (node (ref "C36") (pin "1") (pinfunction "1_1") (pintype "passive"))
      (node (ref "C37") (pin "1") (pinfunction "1_1") (pintype "passive"))
      (node (ref "C38") (pin "1") (pinfunction "1_1") (pintype "passive"))
      (node (ref "C45") (pin "2") (pinfunction "2_2") (pintype "power_in"))
      (node (ref "C46") (pin "2") (pinfunction "2_2") (pintype "power_in"))
      (node (ref "C47") (pin "2") (pinfunction "2_2") (pintype "power_in"))
      (node (ref "C48") (pin "1") (pinfunction "1_1") (pintype "passive"))
      (node (ref "C49") (pin "1") (pinfunction "1_1") (pintype "passive"))
      (node (ref "C50") (pin "1") (pinfunction "1_1") (pintype "passive"))
      (node (ref "R29") (pin "2") (pinfunction "2_2") (pintype "passive"))
      (node (ref "R31") (pin "2") (pinfunction "2_2") (pintype "passive"))
      (node (ref "R33") (pin "2") (pinfunction "2_2") (pintype "passive"))
      (node (ref "R50") (pin "2") (pinfunction "2_2") (pintype "passive"))
      (node (ref "R52") (pin "2") (pinfunction "2_2") (pintype "passive"))
      (node (ref "R54") (pin "2") (pinfunction "2_2") (pintype "passive"))
      (node (ref "VT1") (pin "2") (pinfunction "D_2") (pintype "passive"))
      (node (ref "VT11") (pin "2") (pinfunction "D_2") (pintype "passive"))
      (node (ref "VT3") (pin "2") (pinfunction "D_2") (pintype "passive"))
      (node (ref "VT5") (pin "2") (pinfunction "D_2") (pintype "passive"))
      (node (ref "VT7") (pin "2") (pinfunction "D_2") (pintype "passive"))
      (node (ref "VT9") (pin "2") (pinfunction "D_2") (pintype "passive"))
    )
  )
)
